# MICmuter_v2.net
KiCad netlist of a schematic drawn in Altium Designer
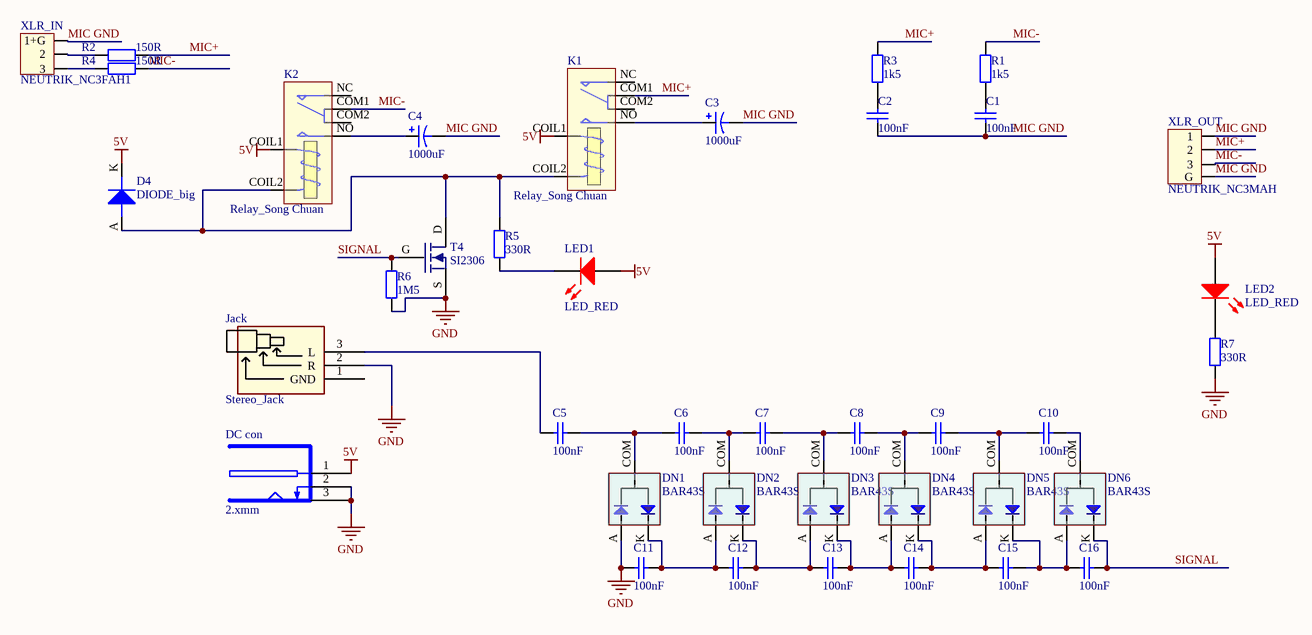
[diagram p0: MICmuter_v2.SchDoc]

(export (version "E")
  (design (tool "Eeschema 10.0.6"))
  (components
    (comp (ref "C1")
      (value "100nF")
      (footprint "FP_0603_CAP_080")
      (description "Capacitor")
      (libsource (lib "Capacitor") (part "CAP"))
    )
    (comp (ref "C2")
      (value "100nF")
      (footprint "FP_0603_CAP_080")
      (description "Capacitor")
      (libsource (lib "Capacitor") (part "CAP"))
    )
    (comp (ref "C3")
      (value "1000uF")
      (footprint "CAP_8x11_allo")
      (description "Polarized Capacitor")
      (libsource (lib "Capacitor") (part "CAP_ELECT"))
    )
    (comp (ref "C4")
      (value "1000uF")
      (footprint "CAP_8x11_allo")
      (description "Polarized Capacitor")
      (libsource (lib "Capacitor") (part "CAP_ELECT"))
    )
    (comp (ref "C5")
      (value "100nF")
      (footprint "FP_0603_CAP_080")
      (description "Capacitor")
      (libsource (lib "Capacitor") (part "CAP"))
    )
    (comp (ref "C6")
      (value "100nF")
      (footprint "FP_0603_CAP_080")
      (description "Capacitor")
      (libsource (lib "Capacitor") (part "CAP"))
    )
    (comp (ref "C7")
      (value "100nF")
      (footprint "FP_0603_CAP_080")
      (description "Capacitor")
      (libsource (lib "Capacitor") (part "CAP"))
    )
    (comp (ref "C8")
      (value "100nF")
      (footprint "FP_0603_CAP_080")
      (description "Capacitor")
      (libsource (lib "Capacitor") (part "CAP"))
    )
    (comp (ref "C9")
      (value "100nF")
      (footprint "FP_0603_CAP_080")
      (description "Capacitor")
      (libsource (lib "Capacitor") (part "CAP"))
    )
    (comp (ref "C10")
      (value "100nF")
      (footprint "FP_0603_CAP_080")
      (description "Capacitor")
      (libsource (lib "Capacitor") (part "CAP"))
    )
    (comp (ref "C11")
      (value "100nF")
      (footprint "FP_0603_CAP_080")
      (description "Capacitor")
      (libsource (lib "Capacitor") (part "CAP"))
    )
    (comp (ref "C12")
      (value "100nF")
      (footprint "FP_0603_CAP_080")
      (description "Capacitor")
      (libsource (lib "Capacitor") (part "CAP"))
    )
    (comp (ref "C13")
      (value "100nF")
      (footprint "FP_0603_CAP_080")
      (description "Capacitor")
      (libsource (lib "Capacitor") (part "CAP"))
    )
    (comp (ref "C14")
      (value "100nF")
      (footprint "FP_0603_CAP_080")
      (description "Capacitor")
      (libsource (lib "Capacitor") (part "CAP"))
    )
    (comp (ref "C15")
      (value "100nF")
      (footprint "FP_0603_CAP_080")
      (description "Capacitor")
      (libsource (lib "Capacitor") (part "CAP"))
    )
    (comp (ref "C16")
      (value "100nF")
      (footprint "FP_0603_CAP_080")
      (description "Capacitor")
      (libsource (lib "Capacitor") (part "CAP"))
    )
    (comp (ref "D4")
      (value "DIODE_big")
      (footprint "FP_SMA DO214AC")
      (libsource (lib "Diode") (part "DIODE_big"))
    )
    (comp (ref "DC con")
      (value "2.xmm")
      (footprint "FP_DC_TAP_ANYA")
      (description "2.xmm DC HEBA25 TÁPFESZÜLTSÉG ALJZAT ZÁRT, NYÁKBA 90°")
      (libsource (lib "Connector") (part "DC_TAP_ANYA"))
    )
    (comp (ref "DN1")
      (value "BAR43S")
      (footprint "DIODE_SOT23_serial")
      (libsource (lib "Diode") (part "BAR43S"))
    )
    (comp (ref "DN2")
      (value "BAR43S")
      (footprint "DIODE_SOT23_serial")
      (libsource (lib "Diode") (part "BAR43S"))
    )
    (comp (ref "DN3")
      (value "BAR43S")
      (footprint "DIODE_SOT23_serial")
      (libsource (lib "Diode") (part "BAR43S"))
    )
    (comp (ref "DN4")
      (value "BAR43S")
      (footprint "DIODE_SOT23_serial")
      (libsource (lib "Diode") (part "BAR43S"))
    )
    (comp (ref "DN5")
      (value "BAR43S")
      (footprint "DIODE_SOT23_serial")
      (libsource (lib "Diode") (part "BAR43S"))
    )
    (comp (ref "DN6")
      (value "BAR43S")
      (footprint "DIODE_SOT23_serial")
      (libsource (lib "Diode") (part "BAR43S"))
    )
    (comp (ref "Jack")
      (value "Stereo_Jack")
      (footprint "STEREO_JACK")
      (libsource (lib "Connector") (part "Stereo_Jack"))
    )
    (comp (ref "K1")
      (value "Relay_Song Chuan")
      (footprint "Relay_Song Chuan")
      (description "SPDT Relay")
      (fields (field (name "PUBLISHER") "Altium Limited"))
      (libsource (lib "Switch") (part "Relay_Song Chuan"))
    )
    (comp (ref "K2")
      (value "Relay_Song Chuan")
      (footprint "Relay_Song Chuan")
      (description "SPDT Relay")
      (fields (field (name "PUBLISHER") "Altium Limited"))
      (libsource (lib "Switch") (part "Relay_Song Chuan"))
    )
    (comp (ref "LED1")
      (value "LED_RED")
      (footprint "Osram sideled")
      (description "Typical LED")
      (libsource (lib "Led_optical") (part "LED_R"))
    )
    (comp (ref "LED2")
      (value "LED_RED")
      (footprint "Osram sideled")
      (description "Typical LED")
      (libsource (lib "Led_optical") (part "LED_R"))
    )
    (comp (ref "R1")
      (value "1k5")
      (footprint "FP_0603_RES")
      (description "Resistor")
      (libsource (lib "Miscellaneous Devices") (part "Res3"))
    )
    (comp (ref "R2")
      (value "150R")
      (footprint "FP_0603_RES")
      (description "Resistor")
      (libsource (lib "") (part "Res3_1"))
    )
    (comp (ref "R3")
      (value "1k5")
      (footprint "FP_0603_RES")
      (description "Resistor")
      (libsource (lib "Miscellaneous Devices") (part "Res3"))
    )
    (comp (ref "R4")
      (value "150R")
      (footprint "FP_0603_RES")
      (description "Resistor")
      (libsource (lib "") (part "Res3_1"))
    )
    (comp (ref "R5")
      (value "330R")
      (footprint "FP_0603_RES")
      (description "Resistor")
      (libsource (lib "Miscellaneous Devices") (part "Res3"))
    )
    (comp (ref "R6")
      (value "1M5")
      (footprint "FP_0603_RES")
      (description "Resistor")
      (libsource (lib "Miscellaneous Devices") (part "Res3"))
    )
    (comp (ref "R7")
      (value "330R")
      (footprint "FP_0603_RES")
      (description "Resistor")
      (libsource (lib "Miscellaneous Devices") (part "Res3"))
    )
    (comp (ref "T4") (value "SI2306") (footprint "FET_SOT23") (libsource (lib "FET") (part "NMOS")))
    (comp (ref "XLR_IN")
      (value "NEUTRIK_NC3FAH1")
      (footprint "NEUTRIK_NC3FAH1")
      (libsource (lib "Connector") (part "NEUTRIK_NC3FAH1"))
    )
    (comp (ref "XLR_OUT")
      (value "NEUTRIK_NC3MAH")
      (footprint "NEUTRIK_NC3MAH")
      (libsource (lib "Connector") (part "NEUTRIK_NC3MAH"))
    )
  )
  (nets
    (net (code "1") (name "/MIC GND") (class "Default")
      (node (ref "C1") (pin "1") (pinfunction "1_1") (pintype "passive"))
      (node (ref "C2") (pin "1") (pinfunction "1_1") (pintype "passive"))
      (node (ref "C3") (pin "N") (pintype "passive"))
      (node (ref "C4") (pin "N") (pintype "passive"))
      (node (ref "XLR_IN") (pin "1+G") (pinfunction "1+G_1+G") (pintype "passive"))
      (node (ref "XLR_OUT") (pin "1") (pinfunction "1_1") (pintype "passive"))
      (node (ref "XLR_OUT") (pin "G") (pinfunction "G_G") (pintype "passive"))
    )
    (net (code "2") (name "/MIC+") (class "Default")
      (node (ref "K1") (pin "COM1") (pinfunction "COM_COM1") (pintype "passive"))
      (node (ref "R2") (pin "1") (pinfunction "1_1") (pintype "passive"))
      (node (ref "R3") (pin "1") (pinfunction "1_1") (pintype "passive"))
      (node (ref "XLR_OUT") (pin "2") (pinfunction "2_2") (pintype "passive"))
    )
    (net (code "3") (name "/MIC-") (class "Default")
      (node (ref "K2") (pin "COM1") (pinfunction "COM_COM1") (pintype "passive"))
      (node (ref "R1") (pin "1") (pinfunction "1_1") (pintype "passive"))
      (node (ref "R4") (pin "1") (pinfunction "1_1") (pintype "passive"))
      (node (ref "XLR_OUT") (pin "3") (pinfunction "3_3") (pintype "passive"))
    )
    (net (code "4") (name "/SIGNAL") (class "Default")
      (node (ref "C16") (pin "1") (pinfunction "1_1") (pintype "passive"))
      (node (ref "DN6") (pin "K") (pinfunction "K_K") (pintype "passive"))
      (node (ref "R6") (pin "1") (pinfunction "1_1") (pintype "passive"))
      (node (ref "T4") (pin "G") (pinfunction "G_G") (pintype "passive"))
    )
    (net (code "5") (name "5V") (class "Default")
      (node (ref "D4") (pin "K") (pinfunction "K_K") (pintype "passive"))
      (node (ref "DC con") (pin "1") (pinfunction "9V_1") (pintype "power_in"))
      (node (ref "K1") (pin "COIL1") (pinfunction "COIL1_COIL1") (pintype "passive"))
      (node (ref "K2") (pin "COIL1") (pinfunction "COIL1_COIL1") (pintype "passive"))
      (node (ref "LED1") (pin "A") (pinfunction "A_A") (pintype "passive"))
      (node (ref "LED2") (pin "A") (pinfunction "A_A") (pintype "passive"))
    )
    (net (code "6") (name "GND") (class "Default")
      (node (ref "C11") (pin "2") (pinfunction "2_2") (pintype "passive"))
      (node (ref "DC con") (pin "2") (pinfunction "GND_2") (pintype "power_in"))
      (node (ref "DC con") (pin "3") (pinfunction "GND_3") (pintype "power_in"))
      (node (ref "DN1") (pin "A") (pinfunction "A_A") (pintype "passive"))
      (node (ref "Jack") (pin "2") (pinfunction "R_2") (pintype "passive"))
      (node (ref "R6") (pin "2") (pinfunction "2_2") (pintype "passive"))
      (node (ref "R7") (pin "2") (pinfunction "2_2") (pintype "passive"))
      (node (ref "T4") (pin "S") (pinfunction "S_S") (pintype "passive"))
    )
    (net (code "7") (name "Net-(C1-Pad2)") (class "Default")
      (node (ref "C1") (pin "2") (pinfunction "2_2") (pintype "passive"))
      (node (ref "R1") (pin "2") (pinfunction "2_2") (pintype "passive"))
    )
    (net (code "8") (name "Net-(C2-Pad2)") (class "Default")
      (node (ref "C2") (pin "2") (pinfunction "2_2") (pintype "passive"))
      (node (ref "R3") (pin "2") (pinfunction "2_2") (pintype "passive"))
    )
    (net (code "9") (name "Net-(C3-PadP)") (class "Default")
      (node (ref "C3") (pin "P") (pintype "passive"))
      (node (ref "K1") (pin "NO") (pinfunction "NO_NO") (pintype "passive"))
    )
    (net (code "10") (name "Net-(C4-PadP)") (class "Default")
      (node (ref "C4") (pin "P") (pintype "passive"))
      (node (ref "K2") (pin "NO") (pinfunction "NO_NO") (pintype "passive"))
    )
    (net (code "11") (name "Net-(C5-Pad1)") (class "Default")
      (node (ref "C5") (pin "1") (pinfunction "1_1") (pintype "passive"))
      (node (ref "C6") (pin "2") (pinfunction "2_2") (pintype "passive"))
      (node (ref "DN1") (pin "COM") (pinfunction "COM_COM") (pintype "passive"))
    )
    (net (code "12") (name "Net-(C6-Pad1)") (class "Default")
      (node (ref "C6") (pin "1") (pinfunction "1_1") (pintype "passive"))
      (node (ref "C7") (pin "2") (pinfunction "2_2") (pintype "passive"))
      (node (ref "DN2") (pin "COM") (pinfunction "COM_COM") (pintype "passive"))
    )
    (net (code "13") (name "Net-(C7-Pad1)") (class "Default")
      (node (ref "C7") (pin "1") (pinfunction "1_1") (pintype "passive"))
      (node (ref "C8") (pin "2") (pinfunction "2_2") (pintype "passive"))
      (node (ref "DN3") (pin "COM") (pinfunction "COM_COM") (pintype "passive"))
    )
    (net (code "14") (name "Net-(C8-Pad1)") (class "Default")
      (node (ref "C8") (pin "1") (pinfunction "1_1") (pintype "passive"))
      (node (ref "C9") (pin "2") (pinfunction "2_2") (pintype "passive"))
      (node (ref "DN4") (pin "COM") (pinfunction "COM_COM") (pintype "passive"))
    )
    (net (code "15") (name "Net-(C10-Pad1)") (class "Default")
      (node (ref "C10") (pin "1") (pinfunction "1_1") (pintype "passive"))
      (node (ref "DN6") (pin "COM") (pinfunction "COM_COM") (pintype "passive"))
    )
    (net (code "16") (name "Net-(C10-Pad2)") (class "Default")
      (node (ref "C10") (pin "2") (pinfunction "2_2") (pintype "passive"))
      (node (ref "C9") (pin "1") (pinfunction "1_1") (pintype "passive"))
      (node (ref "DN5") (pin "COM") (pinfunction "COM_COM") (pintype "passive"))
    )
    (net (code "17") (name "Net-(C11-Pad1)") (class "Default")
      (node (ref "C11") (pin "1") (pinfunction "1_1") (pintype "passive"))
      (node (ref "C12") (pin "2") (pinfunction "2_2") (pintype "passive"))
      (node (ref "DN1") (pin "K") (pinfunction "K_K") (pintype "passive"))
      (node (ref "DN2") (pin "A") (pinfunction "A_A") (pintype "passive"))
    )
    (net (code "18") (name "Net-(C12-Pad1)") (class "Default")
      (node (ref "C12") (pin "1") (pinfunction "1_1") (pintype "passive"))
      (node (ref "C13") (pin "2") (pinfunction "2_2") (pintype "passive"))
      (node (ref "DN2") (pin "K") (pinfunction "K_K") (pintype "passive"))
      (node (ref "DN3") (pin "A") (pinfunction "A_A") (pintype "passive"))
    )
    (net (code "19") (name "Net-(C13-Pad1)") (class "Default")
      (node (ref "C13") (pin "1") (pinfunction "1_1") (pintype "passive"))
      (node (ref "C14") (pin "2") (pinfunction "2_2") (pintype "passive"))
      (node (ref "DN3") (pin "K") (pinfunction "K_K") (pintype "passive"))
      (node (ref "DN4") (pin "A") (pinfunction "A_A") (pintype "passive"))
    )
    (net (code "20") (name "Net-(C14-Pad1)") (class "Default")
      (node (ref "C14") (pin "1") (pinfunction "1_1") (pintype "passive"))
      (node (ref "C15") (pin "2") (pinfunction "2_2") (pintype "passive"))
      (node (ref "DN4") (pin "K") (pinfunction "K_K") (pintype "passive"))
      (node (ref "DN5") (pin "A") (pinfunction "A_A") (pintype "passive"))
    )
    (net (code "21") (name "Net-(C15-Pad1)") (class "Default")
      (node (ref "C15") (pin "1") (pinfunction "1_1") (pintype "passive"))
      (node (ref "C16") (pin "2") (pinfunction "2_2") (pintype "passive"))
      (node (ref "DN5") (pin "K") (pinfunction "K_K") (pintype "passive"))
      (node (ref "DN6") (pin "A") (pinfunction "A_A") (pintype "passive"))
    )
    (net (code "22") (name "Net-(D4-PadA)") (class "Default")
      (node (ref "D4") (pin "A") (pinfunction "A_A") (pintype "passive"))
      (node (ref "K1") (pin "COIL2") (pinfunction "COIL2_COIL2") (pintype "passive"))
      (node (ref "K2") (pin "COIL2") (pinfunction "COIL2_COIL2") (pintype "passive"))
      (node (ref "R5") (pin "1") (pinfunction "1_1") (pintype "passive"))
      (node (ref "T4") (pin "D") (pinfunction "D_D") (pintype "passive"))
    )
    (net (code "23") (name "Net-(Jack-L)") (class "Default")
      (node (ref "C5") (pin "2") (pinfunction "2_2") (pintype "passive"))
      (node (ref "Jack") (pin "3") (pinfunction "L_3") (pintype "passive"))
    )
    (net (code "24") (name "Net-(LED1-PadK)") (class "Default")
      (node (ref "LED1") (pin "K") (pinfunction "K_K") (pintype "passive"))
      (node (ref "R5") (pin "2") (pinfunction "2_2") (pintype "passive"))
    )
    (net (code "25") (name "Net-(LED2-PadK)") (class "Default")
      (node (ref "LED2") (pin "K") (pinfunction "K_K") (pintype "passive"))
      (node (ref "R7") (pin "1") (pinfunction "1_1") (pintype "passive"))
    )
    (net (code "26") (name "Net-(R2-Pad2)") (class "Default")
      (node (ref "R2") (pin "2") (pinfunction "2_2") (pintype "passive"))
      (node (ref "XLR_IN") (pin "2") (pinfunction "2_2") (pintype "passive"))
    )
    (net (code "27") (name "Net-(R4-Pad2)") (class "Default")
      (node (ref "R4") (pin "2") (pinfunction "2_2") (pintype "passive"))
      (node (ref "XLR_IN") (pin "3") (pinfunction "3_3") (pintype "passive"))
    )
    (net (code "28") (name "unconnected-(Jack-GND-Pad1)") (class "Default")
      (node (ref "Jack") (pin "1") (pinfunction "GND_1") (pintype "passive"))
    )
    (net (code "29") (name "unconnected-(K1-COM-PadCOM2)") (class "Default")
      (node (ref "K1") (pin "COM2") (pinfunction "COM_COM2") (pintype "passive"))
    )
    (net (code "30") (name "unconnected-(K1-PadNC)") (class "Default")
      (node (ref "K1") (pin "NC") (pinfunction "NC_NC") (pintype "passive"))
    )
    (net (code "31") (name "unconnected-(K2-COM-PadCOM2)") (class "Default")
      (node (ref "K2") (pin "COM2") (pinfunction "COM_COM2") (pintype "passive"))
    )
    (net (code "32") (name "unconnected-(K2-PadNC)") (class "Default")
      (node (ref "K2") (pin "NC") (pinfunction "NC_NC") (pintype "passive"))
    )
  )
)
